# working.net
KiCad netlist of a schematic drawn in EAGLE
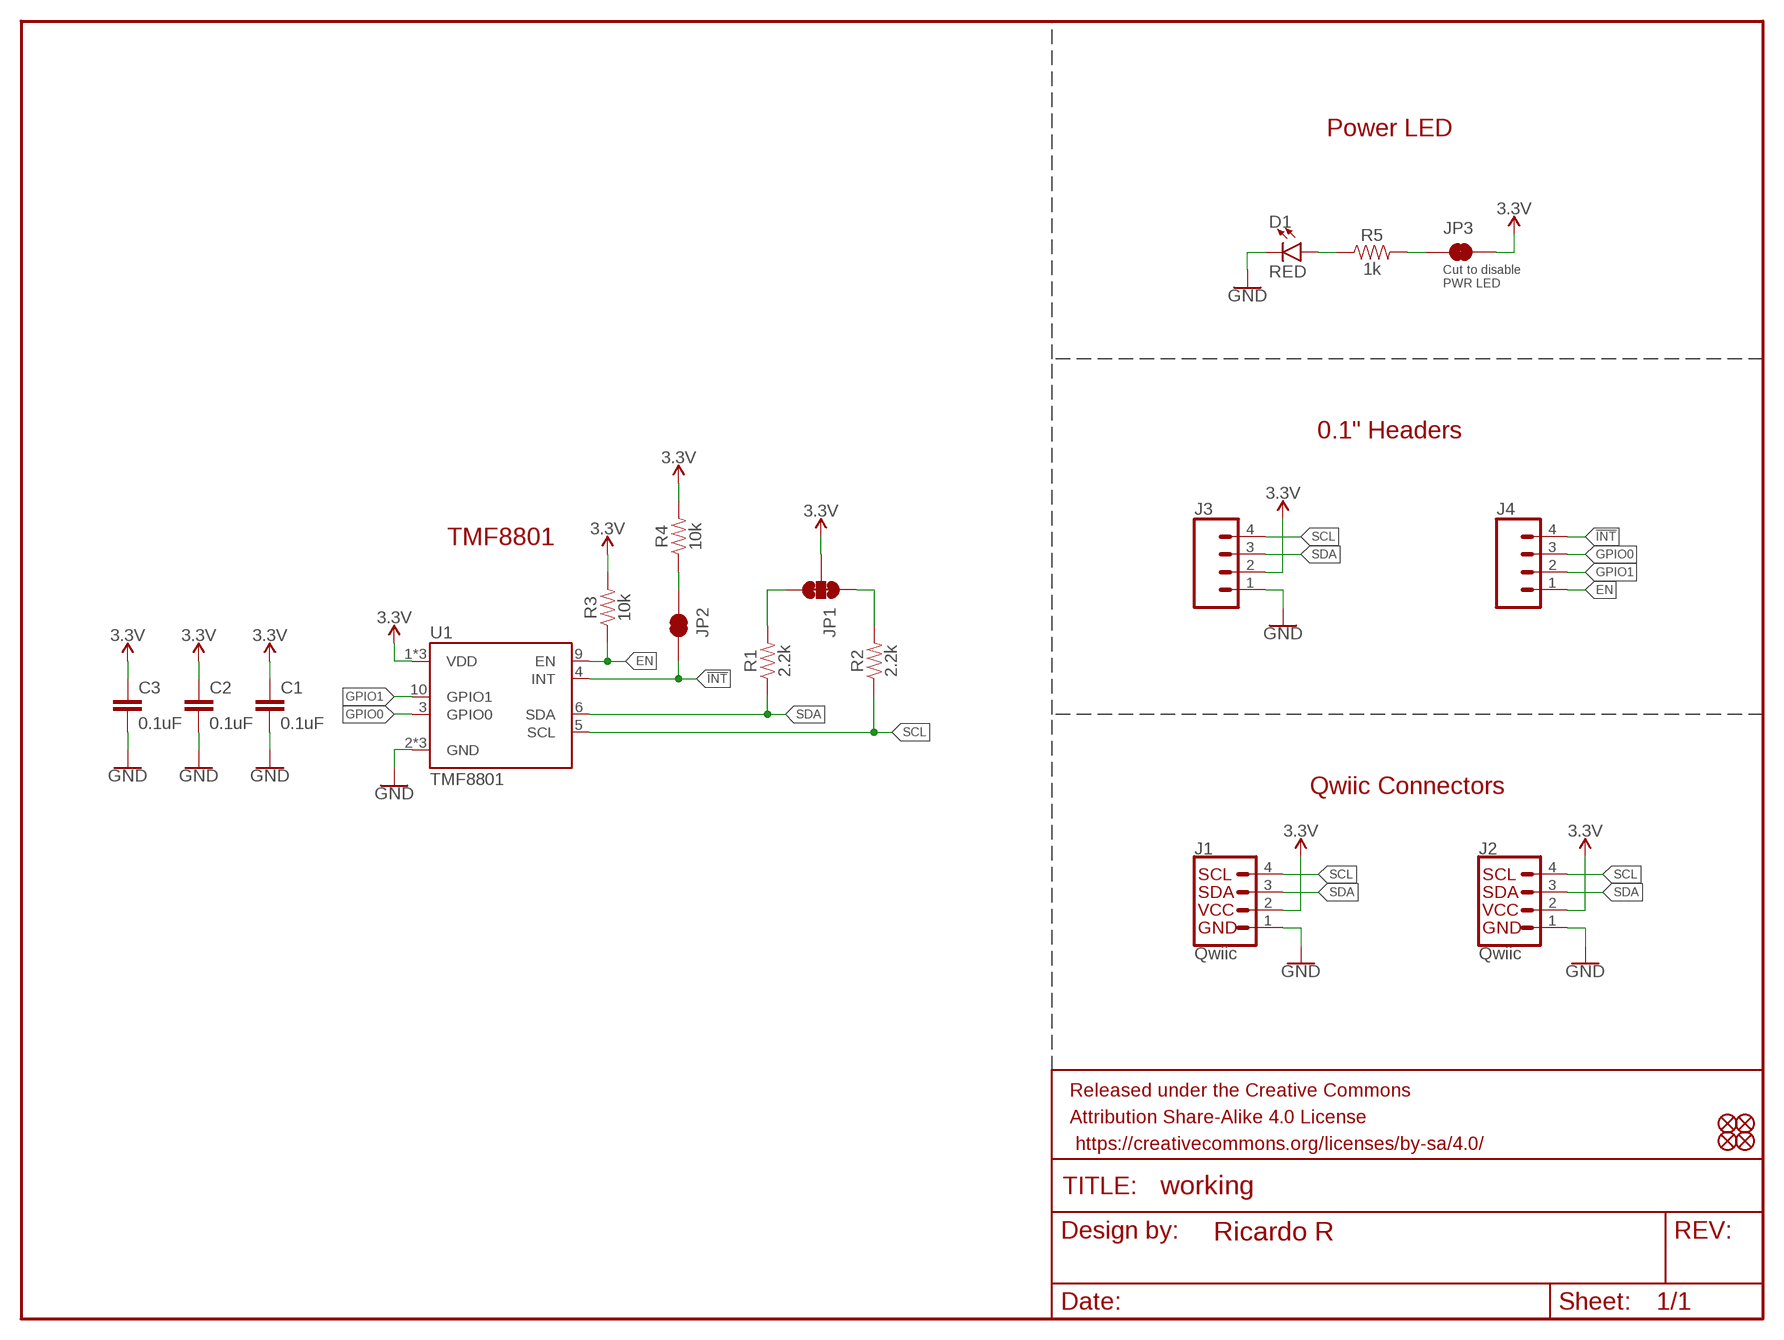
[diagram p0: schematic, sheet 1]

(export (version "E")
  (design (tool "Eeschema 10.0.6"))
  (components
    (comp (ref "C1")
      (value "0.1uF")
      (footprint "eagle-import:0603")
      (libsource (lib "eagle-import") (part "0.1UF-0603-25V-(+80/-20%)"))
    )
    (comp (ref "C2")
      (value "0.1uF")
      (footprint "eagle-import:0603")
      (libsource (lib "eagle-import") (part "0.1UF-0603-25V-(+80/-20%)"))
    )
    (comp (ref "C3")
      (value "0.1uF")
      (footprint "eagle-import:0603")
      (libsource (lib "eagle-import") (part "0.1UF-0603-25V-(+80/-20%)"))
    )
    (comp (ref "D1")
      (value "RED")
      (footprint "eagle-import:LED-0603")
      (libsource (lib "eagle-import") (part "LED-RED0603"))
    )
    (comp (ref "FD1")
      (value "FIDUCIAL1X2")
      (footprint "eagle-import:FIDUCIAL-1X2")
      (libsource (lib "eagle-import") (part "FIDUCIAL1X2"))
    )
    (comp (ref "FD2")
      (value "FIDUCIAL1X2")
      (footprint "eagle-import:FIDUCIAL-1X2")
      (libsource (lib "eagle-import") (part "FIDUCIAL1X2"))
    )
    (comp (ref "FD3")
      (value "FIDUCIAL1X2")
      (footprint "eagle-import:FIDUCIAL-1X2")
      (libsource (lib "eagle-import") (part "FIDUCIAL1X2"))
    )
    (comp (ref "FD4")
      (value "FIDUCIAL1X2")
      (footprint "eagle-import:FIDUCIAL-1X2")
      (libsource (lib "eagle-import") (part "FIDUCIAL1X2"))
    )
    (comp (ref "FRAME1")
      (value "FRAME-LETTERNO_PACKAGE")
      (footprint "eagle-import:DUMMY")
      (fields (field (name "DESIGNER") "Ricardo R") (field (name "DESIGNER_1") "Ricardo R"))
      (libsource (lib "eagle-import") (part "FRAME-LETTERNO_PACKAGE"))
    )
    (comp (ref "J1")
      (value "Qwiic")
      (footprint "eagle-import:JST04_1MM_RA")
      (libsource (lib "eagle-import") (part "QWIIC_CONNECTORJS-1MM"))
    )
    (comp (ref "J2")
      (value "Qwiic")
      (footprint "eagle-import:JST04_1MM_RA")
      (libsource (lib "eagle-import") (part "QWIIC_CONNECTORJS-1MM"))
    )
    (comp (ref "J3")
      (value "CONN_041X04_NO_SILK")
      (footprint "eagle-import:1X04_NO_SILK")
      (libsource (lib "eagle-import") (part "CONN_041X04_NO_SILK"))
    )
    (comp (ref "J4")
      (value "CONN_041X04_NO_SILK")
      (footprint "eagle-import:1X04_NO_SILK")
      (libsource (lib "eagle-import") (part "CONN_041X04_NO_SILK"))
    )
    (comp (ref "JP1")
      (value "JUMPER-SMT_3_2-NC_TRACE_SILK")
      (footprint "eagle-import:SMT-JUMPER_3_2-NC_TRACE_SILK")
      (libsource (lib "eagle-import") (part "JUMPER-SMT_3_2-NC_TRACE_SILK"))
    )
    (comp (ref "JP2")
      (value "JUMPER-SMT_2_NC_TRACE_SILK")
      (footprint "eagle-import:SMT-JUMPER_2_NC_TRACE_SILK")
      (libsource (lib "eagle-import") (part "JUMPER-SMT_2_NC_TRACE_SILK"))
    )
    (comp (ref "JP3")
      (value "JUMPER-SMT_2_NC_TRACE_SILK")
      (footprint "eagle-import:SMT-JUMPER_2_NC_TRACE_SILK")
      (libsource (lib "eagle-import") (part "JUMPER-SMT_2_NC_TRACE_SILK"))
    )
    (comp (ref "R1")
      (value "2.2k")
      (footprint "eagle-import:0603")
      (libsource (lib "eagle-import") (part "2.2KOHM-0603-1/10W-1%"))
    )
    (comp (ref "R2")
      (value "2.2k")
      (footprint "eagle-import:0603")
      (libsource (lib "eagle-import") (part "2.2KOHM-0603-1/10W-1%"))
    )
    (comp (ref "R3")
      (value "10k")
      (footprint "eagle-import:0603")
      (libsource (lib "eagle-import") (part "10KOHM-0603-1/10W-1%"))
    )
    (comp (ref "R4")
      (value "10k")
      (footprint "eagle-import:0603")
      (libsource (lib "eagle-import") (part "10KOHM-0603-1/10W-1%"))
    )
    (comp (ref "R5")
      (value "1k")
      (footprint "eagle-import:0603")
      (libsource (lib "eagle-import") (part "1KOHM-0603-1/10W-1%"))
    )
    (comp (ref "U1")
      (value "TMF8801")
      (footprint "eagle-import:TMF8801-CUSTOM")
      (libsource (lib "eagle-import") (part "TMF8801TMF8801"))
    )
  )
  (nets
    (net (code "1") (name "/~{INT}") (class "Default")
      (node (ref "J4") (pin "4") (pinfunction "4_4") (pintype "passive"))
      (node (ref "JP2") (pin "2") (pinfunction "2_2") (pintype "passive"))
      (node (ref "U1") (pin "4") (pinfunction "INT_4") (pintype "open_collector"))
    )
    (net (code "2") (name "3.3V") (class "Default")
      (node (ref "C1") (pin "1") (pinfunction "1_1") (pintype "passive"))
      (node (ref "C2") (pin "1") (pinfunction "1_1") (pintype "passive"))
      (node (ref "C3") (pin "1") (pinfunction "1_1") (pintype "passive"))
      (node (ref "J1") (pin "2") (pinfunction "2_2") (pintype "power_in"))
      (node (ref "J2") (pin "2") (pinfunction "2_2") (pintype "power_in"))
      (node (ref "J3") (pin "2") (pinfunction "2_2") (pintype "passive"))
      (node (ref "JP1") (pin "2") (pinfunction "2_2") (pintype "passive"))
      (node (ref "JP3") (pin "2") (pinfunction "2_2") (pintype "passive"))
      (node (ref "R3") (pin "2") (pinfunction "2_2") (pintype "passive"))
      (node (ref "R4") (pin "2") (pinfunction "2_2") (pintype "passive"))
      (node (ref "U1") (pin "1") (pinfunction "VDD_1") (pintype "power_in"))
      (node (ref "U1") (pin "12") (pinfunction "VDD_12") (pintype "power_in"))
      (node (ref "U1") (pin "7") (pinfunction "VDD_7") (pintype "power_in"))
    )
    (net (code "3") (name "EN") (class "Default")
      (node (ref "J4") (pin "1") (pinfunction "1_1") (pintype "passive"))
      (node (ref "R3") (pin "1") (pinfunction "1_1") (pintype "passive"))
      (node (ref "U1") (pin "9") (pinfunction "EN_9") (pintype "input"))
    )
    (net (code "4") (name "GND") (class "Default")
      (node (ref "C1") (pin "2") (pinfunction "2_2") (pintype "passive"))
      (node (ref "C2") (pin "2") (pinfunction "2_2") (pintype "passive"))
      (node (ref "C3") (pin "2") (pinfunction "2_2") (pintype "passive"))
      (node (ref "D1") (pin "C") (pinfunction "C_C") (pintype "passive"))
      (node (ref "J1") (pin "1") (pinfunction "1_1") (pintype "power_in"))
      (node (ref "J2") (pin "1") (pinfunction "1_1") (pintype "power_in"))
      (node (ref "J3") (pin "1") (pinfunction "1_1") (pintype "passive"))
      (node (ref "U1") (pin "11") (pinfunction "GND_11") (pintype "power_in"))
      (node (ref "U1") (pin "2") (pinfunction "GND_2") (pintype "power_in"))
      (node (ref "U1") (pin "8") (pinfunction "GND_8") (pintype "power_in"))
    )
    (net (code "5") (name "GPIO0") (class "Default")
      (node (ref "J4") (pin "3") (pinfunction "3_3") (pintype "passive"))
      (node (ref "U1") (pin "3") (pinfunction "GPIO0_3") (pintype "bidirectional"))
    )
    (net (code "6") (name "GPIO1") (class "Default")
      (node (ref "J4") (pin "2") (pinfunction "2_2") (pintype "passive"))
      (node (ref "U1") (pin "10") (pinfunction "GPIO1_10") (pintype "bidirectional"))
    )
    (net (code "7") (name "Net-(D1-PadA)") (class "Default")
      (node (ref "D1") (pin "A") (pinfunction "A_A") (pintype "passive"))
      (node (ref "R5") (pin "1") (pinfunction "1_1") (pintype "passive"))
    )
    (net (code "8") (name "Net-(JP1-Pad1)") (class "Default")
      (node (ref "JP1") (pin "1") (pinfunction "1_1") (pintype "passive"))
      (node (ref "R2") (pin "2") (pinfunction "2_2") (pintype "passive"))
    )
    (net (code "9") (name "Net-(JP1-Pad3)") (class "Default")
      (node (ref "JP1") (pin "3") (pinfunction "3_3") (pintype "passive"))
      (node (ref "R1") (pin "2") (pinfunction "2_2") (pintype "passive"))
    )
    (net (code "10") (name "Net-(JP2-Pad1)") (class "Default")
      (node (ref "JP2") (pin "1") (pinfunction "1_1") (pintype "passive"))
      (node (ref "R4") (pin "1") (pinfunction "1_1") (pintype "passive"))
    )
    (net (code "11") (name "Net-(JP3-Pad1)") (class "Default")
      (node (ref "JP3") (pin "1") (pinfunction "1_1") (pintype "passive"))
      (node (ref "R5") (pin "2") (pinfunction "2_2") (pintype "passive"))
    )
    (net (code "12") (name "SCL") (class "Default")
      (node (ref "J1") (pin "4") (pinfunction "4_4") (pintype "passive"))
      (node (ref "J2") (pin "4") (pinfunction "4_4") (pintype "passive"))
      (node (ref "J3") (pin "4") (pinfunction "4_4") (pintype "passive"))
      (node (ref "R2") (pin "1") (pinfunction "1_1") (pintype "passive"))
      (node (ref "U1") (pin "5") (pinfunction "SCL_5") (pintype "bidirectional"))
    )
    (net (code "13") (name "SDA") (class "Default")
      (node (ref "J1") (pin "3") (pinfunction "3_3") (pintype "passive"))
      (node (ref "J2") (pin "3") (pinfunction "3_3") (pintype "passive"))
      (node (ref "J3") (pin "3") (pinfunction "3_3") (pintype "passive"))
      (node (ref "R1") (pin "1") (pinfunction "1_1") (pintype "passive"))
      (node (ref "U1") (pin "6") (pinfunction "SDA_6") (pintype "bidirectional"))
    )
  )
)
